# Connector.net
KiCad netlist of a schematic drawn in Altium Designer
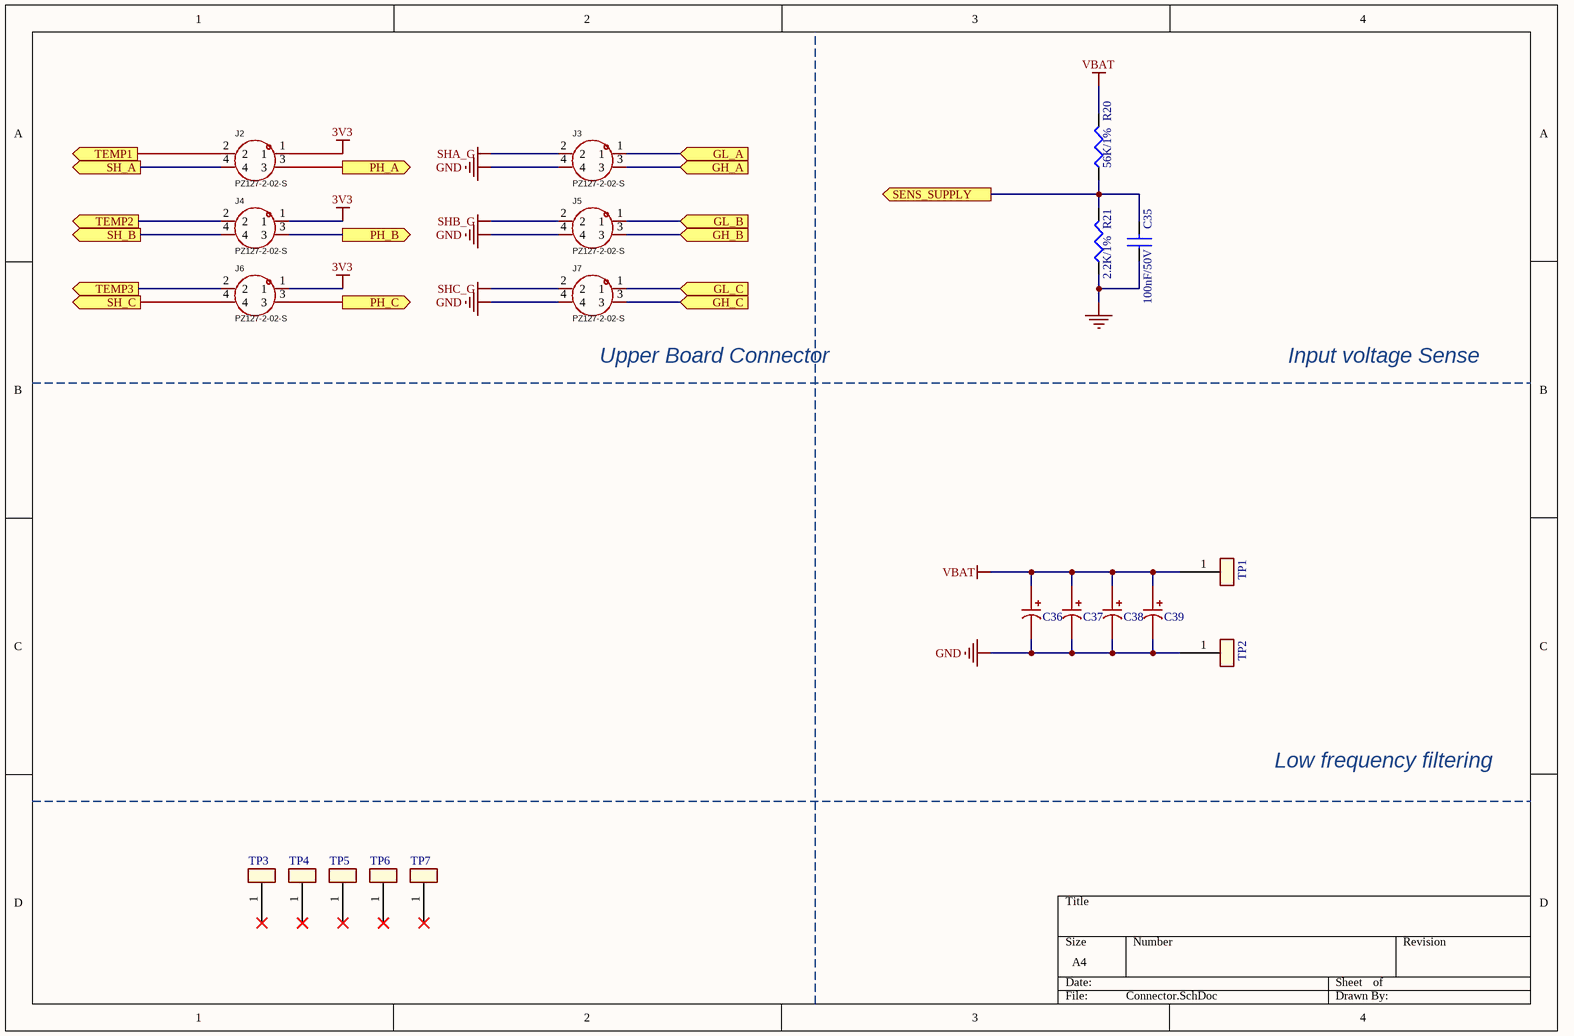
[diagram p0: Connector.SchDoc]

(export (version "E")
  (design (tool "Eeschema 10.0.6"))
  (components
    (comp (ref "C35") (value "100nF/50V") (footprint "C0402") (libsource (lib "*") (part "CAP NP")))
    (comp (ref "C36")
      (value "680uF")
      (footprint "CAP-TH_10.0x17mm")
      (description "容值:680uF;精度:±20%;额定电压:35V;纹波电流:-;等效串联电阻:-;")
      (fields (field (name "MANUFACTURER") "AISHI(艾华集团)") (field (name "MANUFACTURER PART") "ERS1VM681G16OT"))
      (libsource (lib "VESC_DEVICE_Library") (part "ERS1VM681G16OT"))
    )
    (comp (ref "C37")
      (value "680uF")
      (footprint "CAP-TH_10.0x17mm")
      (description "容值:680uF;精度:±20%;额定电压:35V;纹波电流:-;等效串联电阻:-;")
      (fields (field (name "MANUFACTURER") "AISHI(艾华集团)") (field (name "MANUFACTURER PART") "ERS1VM681G16OT"))
      (libsource (lib "VESC_DEVICE_Library") (part "ERS1VM681G16OT"))
    )
    (comp (ref "C38")
      (value "680uF")
      (footprint "CAP-TH_10.0x17mm")
      (description "容值:680uF;精度:±20%;额定电压:35V;纹波电流:-;等效串联电阻:-;")
      (fields (field (name "MANUFACTURER") "AISHI(艾华集团)") (field (name "MANUFACTURER PART") "ERS1VM681G16OT"))
      (libsource (lib "VESC_DEVICE_Library") (part "ERS1VM681G16OT"))
    )
    (comp (ref "C39")
      (value "680uF")
      (footprint "CAP-TH_10.0x17mm")
      (description "容值:680uF;精度:±20%;额定电压:35V;纹波电流:-;等效串联电阻:-;")
      (fields (field (name "MANUFACTURER") "AISHI(艾华集团)") (field (name "MANUFACTURER PART") "ERS1VM681G16OT"))
      (libsource (lib "VESC_DEVICE_Library") (part "ERS1VM681G16OT"))
    )
    (comp (ref "J2")
      (value "PZ127-2-02-S")
      (footprint "HDR-SMD_4P-P1.27-V-M-R2-C2-LS5.3")
      (fields (field (name "MANUFACTURER") "HCTL(华灿天禄)"))
      (libsource (lib "VESC_DEVICE_Library") (part "PZ127-2-02-S"))
    )
    (comp (ref "J3")
      (value "PZ127-2-02-S")
      (footprint "HDR-SMD_4P-P1.27-V-M-R2-C2-LS5.3")
      (fields (field (name "MANUFACTURER") "HCTL(华灿天禄)"))
      (libsource (lib "VESC_DEVICE_Library") (part "PZ127-2-02-S"))
    )
    (comp (ref "J4")
      (value "PZ127-2-02-S")
      (footprint "HDR-SMD_4P-P1.27-V-M-R2-C2-LS5.3")
      (fields (field (name "MANUFACTURER") "HCTL(华灿天禄)"))
      (libsource (lib "VESC_DEVICE_Library") (part "PZ127-2-02-S"))
    )
    (comp (ref "J5")
      (value "PZ127-2-02-S")
      (footprint "HDR-SMD_4P-P1.27-V-M-R2-C2-LS5.3")
      (fields (field (name "MANUFACTURER") "HCTL(华灿天禄)"))
      (libsource (lib "VESC_DEVICE_Library") (part "PZ127-2-02-S"))
    )
    (comp (ref "J6")
      (value "PZ127-2-02-S")
      (footprint "HDR-SMD_4P-P1.27-V-M-R2-C2-LS5.3")
      (fields (field (name "MANUFACTURER") "HCTL(华灿天禄)"))
      (libsource (lib "VESC_DEVICE_Library") (part "PZ127-2-02-S"))
    )
    (comp (ref "J7")
      (value "PZ127-2-02-S")
      (footprint "HDR-SMD_4P-P1.27-V-M-R2-C2-LS5.3")
      (fields (field (name "MANUFACTURER") "HCTL(华灿天禄)"))
      (libsource (lib "VESC_DEVICE_Library") (part "PZ127-2-02-S"))
    )
    (comp (ref "R20") (value "56K/1%") (footprint "R0402") (libsource (lib "*") (part "RESISTOR")))
    (comp (ref "R21") (value "2.2K/1%") (footprint "R0402") (libsource (lib "*") (part "RESISTOR")))
    (comp (ref "TP1")
      (value "TEST POINT")
      (footprint "HOLE-4MM_M")
      (libsource (lib "") (part "TEST POINT_1"))
    )
    (comp (ref "TP2")
      (value "TEST POINT")
      (footprint "HOLE-4MM_M")
      (libsource (lib "") (part "TEST POINT_1"))
    )
    (comp (ref "TP3")
      (value "TEST POINT")
      (footprint "HOLE-6.2MM_M")
      (libsource (lib "VESC_DEVICE_Library") (part "TEST POINT"))
    )
    (comp (ref "TP4")
      (value "TEST POINT")
      (footprint "HOLE-6.2MM_M")
      (libsource (lib "VESC_DEVICE_Library") (part "TEST POINT"))
    )
    (comp (ref "TP5")
      (value "TEST POINT")
      (footprint "HOLE-6.2MM_M")
      (libsource (lib "VESC_DEVICE_Library") (part "TEST POINT"))
    )
    (comp (ref "TP6")
      (value "TEST POINT")
      (footprint "HOLE-6.2MM_M")
      (libsource (lib "VESC_DEVICE_Library") (part "TEST POINT"))
    )
    (comp (ref "TP7")
      (value "TEST POINT")
      (footprint "HOLE-6.2MM_M")
      (libsource (lib "VESC_DEVICE_Library") (part "TEST POINT"))
    )
  )
  (nets
    (net (code "1") (name "/GH_A") (class "Default")
      (node (ref "J3") (pin "3") (pinfunction "3_3") (pintype "passive"))
    )
    (net (code "2") (name "/GH_B") (class "Default")
      (node (ref "J5") (pin "3") (pinfunction "3_3") (pintype "passive"))
    )
    (net (code "3") (name "/GH_C") (class "Default")
      (node (ref "J7") (pin "3") (pinfunction "3_3") (pintype "passive"))
    )
    (net (code "4") (name "/GL_A") (class "Default")
      (node (ref "J3") (pin "1") (pinfunction "1_1") (pintype "passive"))
    )
    (net (code "5") (name "/GL_B") (class "Default")
      (node (ref "J5") (pin "1") (pinfunction "1_1") (pintype "passive"))
    )
    (net (code "6") (name "/GL_C") (class "Default")
      (node (ref "J7") (pin "1") (pinfunction "1_1") (pintype "passive"))
    )
    (net (code "7") (name "/PH_A") (class "Default")
      (node (ref "J2") (pin "3") (pinfunction "3_3") (pintype "passive"))
    )
    (net (code "8") (name "/PH_B") (class "Default")
      (node (ref "J4") (pin "3") (pinfunction "3_3") (pintype "passive"))
    )
    (net (code "9") (name "/PH_C") (class "Default")
      (node (ref "J6") (pin "3") (pinfunction "3_3") (pintype "passive"))
    )
    (net (code "10") (name "/SENS_SUPPLY") (class "Default")
      (node (ref "C35") (pin "2") (pinfunction "2_2") (pintype "passive"))
      (node (ref "R20") (pin "1") (pinfunction "1_1") (pintype "passive"))
      (node (ref "R21") (pin "2") (pinfunction "2_2") (pintype "passive"))
    )
    (net (code "11") (name "/SH_A") (class "Default")
      (node (ref "J2") (pin "4") (pinfunction "4_4") (pintype "passive"))
    )
    (net (code "12") (name "/SH_B") (class "Default")
      (node (ref "J4") (pin "4") (pinfunction "4_4") (pintype "passive"))
    )
    (net (code "13") (name "/SH_C") (class "Default")
      (node (ref "J6") (pin "4") (pinfunction "4_4") (pintype "passive"))
    )
    (net (code "14") (name "/TEMP1") (class "Default")
      (node (ref "J2") (pin "2") (pinfunction "2_2") (pintype "passive"))
    )
    (net (code "15") (name "/TEMP2") (class "Default")
      (node (ref "J4") (pin "2") (pinfunction "2_2") (pintype "passive"))
    )
    (net (code "16") (name "/TEMP3") (class "Default")
      (node (ref "J6") (pin "2") (pinfunction "2_2") (pintype "passive"))
    )
    (net (code "17") (name "3V3") (class "Default")
      (node (ref "J2") (pin "1") (pinfunction "1_1") (pintype "passive"))
      (node (ref "J4") (pin "1") (pinfunction "1_1") (pintype "passive"))
      (node (ref "J6") (pin "1") (pinfunction "1_1") (pintype "passive"))
    )
    (net (code "18") (name "GND") (class "Default")
      (node (ref "C35") (pin "1") (pinfunction "1_1") (pintype "passive"))
      (node (ref "C36") (pin "2") (pinfunction "2_2") (pintype "passive"))
      (node (ref "C37") (pin "2") (pinfunction "2_2") (pintype "passive"))
      (node (ref "C38") (pin "2") (pinfunction "2_2") (pintype "passive"))
      (node (ref "C39") (pin "2") (pinfunction "2_2") (pintype "passive"))
      (node (ref "J3") (pin "4") (pinfunction "4_4") (pintype "passive"))
      (node (ref "J5") (pin "4") (pinfunction "4_4") (pintype "passive"))
      (node (ref "J7") (pin "4") (pinfunction "4_4") (pintype "passive"))
      (node (ref "R21") (pin "1") (pinfunction "1_1") (pintype "passive"))
      (node (ref "TP2") (pin "1") (pinfunction "1_1") (pintype "passive"))
    )
    (net (code "19") (name "SHA_G") (class "Default")
      (node (ref "J3") (pin "2") (pinfunction "2_2") (pintype "passive"))
    )
    (net (code "20") (name "SHB_G") (class "Default")
      (node (ref "J5") (pin "2") (pinfunction "2_2") (pintype "passive"))
    )
    (net (code "21") (name "SHC_G") (class "Default")
      (node (ref "J7") (pin "2") (pinfunction "2_2") (pintype "passive"))
    )
    (net (code "22") (name "VBAT") (class "Default")
      (node (ref "C36") (pin "1") (pinfunction "1_1") (pintype "passive"))
      (node (ref "C37") (pin "1") (pinfunction "1_1") (pintype "passive"))
      (node (ref "C38") (pin "1") (pinfunction "1_1") (pintype "passive"))
      (node (ref "C39") (pin "1") (pinfunction "1_1") (pintype "passive"))
      (node (ref "R20") (pin "2") (pinfunction "2_2") (pintype "passive"))
      (node (ref "TP1") (pin "1") (pinfunction "1_1") (pintype "passive"))
    )
    (net (code "23") (name "unconnected-(TP3-Pad1)") (class "Default")
      (node (ref "TP3") (pin "1") (pinfunction "1_1") (pintype "passive+no_connect"))
    )
    (net (code "24") (name "unconnected-(TP4-Pad1)") (class "Default")
      (node (ref "TP4") (pin "1") (pinfunction "1_1") (pintype "passive+no_connect"))
    )
    (net (code "25") (name "unconnected-(TP5-Pad1)") (class "Default")
      (node (ref "TP5") (pin "1") (pinfunction "1_1") (pintype "passive+no_connect"))
    )
    (net (code "26") (name "unconnected-(TP6-Pad1)") (class "Default")
      (node (ref "TP6") (pin "1") (pinfunction "1_1") (pintype "passive+no_connect"))
    )
    (net (code "27") (name "unconnected-(TP7-Pad1)") (class "Default")
      (node (ref "TP7") (pin "1") (pinfunction "1_1") (pintype "passive+no_connect"))
    )
  )
)
